# Usb.net
KiCad netlist of a schematic drawn in Altium Designer
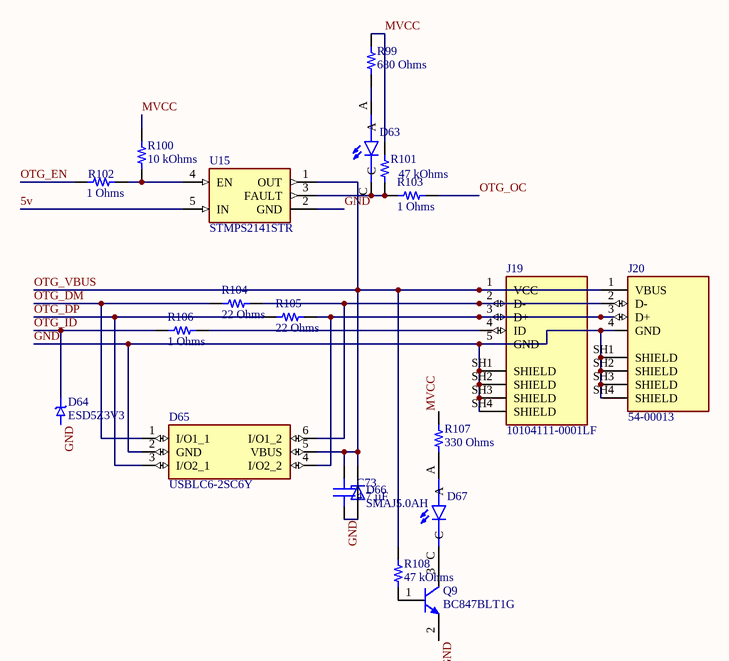
[diagram p0: Usb.SchDoc]

(export (version "E")
  (design (tool "Eeschema 10.0.6"))
  (components
    (comp (ref "C73")
      (value "4.7 µF")
      (footprint "CAP 0805_2012")
      (description "4.70UF 25.0V")
      (fields
        (field (name "PART NUMBER") "C0805X475M3RAC7800")
        (field (name "CAPACITANCE") "4.7 µF")
        (field (name "MANUFACTURER") "KEMET")
      )
      (libsource (lib "Celestial Altium Library - altium_library") (part "Capacitor"))
    )
    (comp (ref "D63")
      (value "597-3305-607F")
      (footprint "LEDC2012X70N")
      (description "LED Uni-Color Green 4-Pin Chip 0805 T/R")
      (libsource (lib "597-3305-607F") (part "597-3305-607F"))
    )
    (comp (ref "D64")
      (value "ESD5Z3V3")
      (footprint "SOD-523_DIOTEC-SEMICONDUCTOR")
      (description "ESD, SOD-523, 0.05ÂµA, 3.3V, Unidir")
      (fields (field (name "MF") "Diotec Semiconductor"))
      (libsource (lib "ESD5Z3V3") (part "ESD5Z3V3"))
    )
    (comp (ref "D65")
      (value "USBLC6-2SC6Y")
      (footprint "SOT95P280X145-6N")
      (description "17V Clamp 5A (8/20µs) Ipp Tvs Diode Surface Mount SOT-23-6")
      (fields (field (name "MF") "STMicroelectronics"))
      (libsource (lib "USBLC6-2SC6Y") (part "USBLC6-2SC6Y"))
    )
    (comp (ref "D66")
      (value "SMAJ5.0AH")
      (footprint "DIOM4325X250N")
      (libsource (lib "SMAJ5.0AH") (part "SMAJ5.0AH"))
    )
    (comp (ref "D67")
      (value "597-3305-607F")
      (footprint "LEDC2012X70N")
      (description "LED Uni-Color Green 4-Pin Chip 0805 T/R")
      (libsource (lib "597-3305-607F") (part "597-3305-607F"))
    )
    (comp (ref "J19")
      (value "10104111-0001LF")
      (footprint "AMPHENOL_10104111-0001LF")
      (fields (field (name "MF") "Amphenol"))
      (libsource (lib "10104111-0001LF") (part "10104111-0001LF"))
    )
    (comp (ref "J20")
      (value "54-00013")
      (footprint "TENSILITY_54-00013")
      (description "Connector, USB A Jack, PCB side-mount, 90 degrees, nickel shell, board lock, black insulator, tray")
      (fields (field (name "MF") "Tensility International Corporation"))
      (libsource (lib "54-00013") (part "54-00013"))
    )
    (comp (ref "Q9")
      (value "BC847BLT1G")
      (footprint "ON SEMI SOT-23-3")
      (description "TRANS NPN 45V 0.1A SOT23")
      (fields (field (name "MANUFACTURER") "ON Semiconductor"))
      (libsource (lib "Celestial Altium Library - altium_library") (part "ON SEMI NPN SOT-23-3"))
    )
    (comp (ref "R99")
      (value "680 Ohms")
      (footprint "RES 0805_2012")
      (description "RES SMD 680 OHM 0.5% 1/4W 0805")
      (fields
        (field (name "PART NUMBER") "RNCF0805DTE680R")
        (field (name "MANUFACTURER") "Stackpole Electronics Inc")
      )
      (libsource (lib "Celestial Altium Library - altium_library") (part "Resistor"))
    )
    (comp (ref "R100")
      (value "10 kOhms")
      (footprint "YAGEO RES 0805_2012")
      (description "RES SMD 10K OHM 0.5% 1/8W 0805")
      (fields (field (name "PART NUMBER") "RT0805DRD0710KL") (field (name "MANUFACTURER") "Yageo"))
      (libsource (lib "Celestial Altium Library - altium_library") (part "Resistor"))
    )
    (comp (ref "R101")
      (value "47 kOhms")
      (footprint "YAGEO RES 0805_2012")
      (description "RES SMD 47K OHM 0.5% 1/8W 0805")
      (fields (field (name "PART NUMBER") "RT0805DRD0747KL") (field (name "MANUFACTURER") "Yageo"))
      (libsource (lib "Celestial Altium Library - altium_library") (part "Resistor"))
    )
    (comp (ref "R102")
      (value "1 Ohms")
      (footprint "RES 0805_2012")
      (description "RES 1 OHM 1% 1/4W 0805")
      (fields
        (field (name "PART NUMBER") "CSR0805FK1R00")
        (field (name "MANUFACTURER") "Stackpole Electronics Inc")
      )
      (libsource (lib "Celestial Altium Library - altium_library") (part "Resistor"))
    )
    (comp (ref "R103")
      (value "1 Ohms")
      (footprint "RES 0805_2012")
      (description "RES 1 OHM 1% 1/4W 0805")
      (fields
        (field (name "PART NUMBER") "CSR0805FK1R00")
        (field (name "MANUFACTURER") "Stackpole Electronics Inc")
      )
      (libsource (lib "Celestial Altium Library - altium_library") (part "Resistor"))
    )
    (comp (ref "R104")
      (value "22 Ohms")
      (footprint "RES 0805_2012")
      (description "RES 22 OHM 5% 1/3W 0805")
      (fields
        (field (name "PART NUMBER") "CRGH0805J22R")
        (field (name "MANUFACTURER") "TE Connectivity Passive Product")
      )
      (libsource (lib "Celestial Altium Library - altium_library") (part "Resistor"))
    )
    (comp (ref "R105")
      (value "22 Ohms")
      (footprint "RES 0805_2012")
      (description "RES 22 OHM 5% 1/3W 0805")
      (fields
        (field (name "PART NUMBER") "CRGH0805J22R")
        (field (name "MANUFACTURER") "TE Connectivity Passive Product")
      )
      (libsource (lib "Celestial Altium Library - altium_library") (part "Resistor"))
    )
    (comp (ref "R106")
      (value "1 Ohms")
      (footprint "RES 0805_2012")
      (description "RES 1 OHM 1% 1/4W 0805")
      (fields
        (field (name "PART NUMBER") "CSR0805FK1R00")
        (field (name "MANUFACTURER") "Stackpole Electronics Inc")
      )
      (libsource (lib "Celestial Altium Library - altium_library") (part "Resistor"))
    )
    (comp (ref "R107")
      (value "330 Ohms")
      (footprint "RES 0805_2012")
      (description "RES SMD 330 OHM 1% 1/2W 0805")
      (fields (field (name "PART NUMBER") "CRCW0805330RFKEAHP") (field (name "MANUFACTURER") "Vishay Dale"))
      (libsource (lib "Celestial Altium Library - altium_library") (part "Resistor"))
    )
    (comp (ref "R108")
      (value "47 kOhms")
      (footprint "YAGEO RES 0805_2012")
      (description "RES SMD 47K OHM 0.5% 1/8W 0805")
      (fields (field (name "PART NUMBER") "RT0805DRD0747KL") (field (name "MANUFACTURER") "Yageo"))
      (libsource (lib "Celestial Altium Library - altium_library") (part "Resistor"))
    )
    (comp (ref "U15")
      (value "STMPS2141STR")
      (footprint "SOT95P280X145-5N")
      (description "Power Switch/Driver 1:1 N-Channel 500mA SOT-23-5")
      (fields (field (name "DIGI-KEY_PART_NUMBER") "497-6933-2-ND") (field (name "MF") "STMicroelectronics"))
      (libsource (lib "STMPS2141STR") (part "STMPS2141STR"))
    )
  )
  (nets
    (net (code "1") (name "/5v") (class "Default")
      (node (ref "U15") (pin "5") (pinfunction "IN_5") (pintype "input"))
    )
    (net (code "2") (name "/GND") (class "Default")
      (node (ref "C73") (pin "1") (pinfunction "1_1") (pintype "passive"))
      (node (ref "D64") (pin "2") (pinfunction "A_2") (pintype "passive"))
      (node (ref "D65") (pin "2") (pinfunction "GND_2") (pintype "bidirectional"))
      (node (ref "D66") (pin "A") (pinfunction "A_A") (pintype "passive"))
      (node (ref "J19") (pin "5") (pinfunction "GND_5") (pintype "power_in"))
      (node (ref "J19") (pin "SH1") (pinfunction "SHIELD_SH1") (pintype "passive"))
      (node (ref "J19") (pin "SH2") (pinfunction "SHIELD_SH2") (pintype "passive"))
      (node (ref "J19") (pin "SH3") (pinfunction "SHIELD_SH3") (pintype "passive"))
      (node (ref "J19") (pin "SH4") (pinfunction "SHIELD_SH4") (pintype "passive"))
      (node (ref "J20") (pin "4") (pinfunction "GND_4") (pintype "power_in"))
      (node (ref "J20") (pin "SH1") (pinfunction "SHIELD_SH1") (pintype "passive"))
      (node (ref "J20") (pin "SH2") (pinfunction "SHIELD_SH2") (pintype "passive"))
      (node (ref "J20") (pin "SH3") (pinfunction "SHIELD_SH3") (pintype "passive"))
      (node (ref "J20") (pin "SH4") (pinfunction "SHIELD_SH4") (pintype "passive"))
      (node (ref "Q9") (pin "2") (pinfunction "E_2") (pintype "passive"))
      (node (ref "U15") (pin "2") (pinfunction "GND_2") (pintype "power_in"))
    )
    (net (code "3") (name "/MVCC") (class "Default")
      (node (ref "R100") (pin "2") (pinfunction "2_2") (pintype "passive"))
      (node (ref "R101") (pin "2") (pinfunction "2_2") (pintype "passive"))
      (node (ref "R107") (pin "2") (pinfunction "2_2") (pintype "passive"))
      (node (ref "R99") (pin "2") (pinfunction "2_2") (pintype "passive"))
    )
    (net (code "4") (name "/OTG_DM") (class "Default")
      (node (ref "D65") (pin "1") (pinfunction "I/O1_1_1") (pintype "bidirectional"))
      (node (ref "R104") (pin "1") (pinfunction "1_1") (pintype "passive"))
    )
    (net (code "5") (name "/OTG_DP") (class "Default")
      (node (ref "D65") (pin "3") (pinfunction "I/O2_1_3") (pintype "bidirectional"))
      (node (ref "R105") (pin "1") (pinfunction "1_1") (pintype "passive"))
    )
    (net (code "6") (name "/OTG_EN") (class "Default")
      (node (ref "R102") (pin "1") (pinfunction "1_1") (pintype "passive"))
    )
    (net (code "7") (name "/OTG_ID") (class "Default")
      (node (ref "D64") (pin "1") (pinfunction "C_1") (pintype "passive"))
      (node (ref "R106") (pin "1") (pinfunction "1_1") (pintype "passive"))
    )
    (net (code "8") (name "/OTG_OC") (class "Default")
      (node (ref "R103") (pin "2") (pinfunction "2_2") (pintype "passive"))
    )
    (net (code "9") (name "/OTG_VBUS") (class "Default")
      (node (ref "C73") (pin "2") (pinfunction "2_2") (pintype "passive"))
      (node (ref "D65") (pin "5") (pinfunction "VBUS_5") (pintype "bidirectional"))
      (node (ref "D66") (pin "C") (pinfunction "C_C") (pintype "passive"))
      (node (ref "J19") (pin "1") (pinfunction "VCC_1") (pintype "power_in"))
      (node (ref "J20") (pin "1") (pinfunction "VBUS_1") (pintype "power_in"))
      (node (ref "R108") (pin "2") (pinfunction "2_2") (pintype "passive"))
      (node (ref "U15") (pin "1") (pinfunction "OUT_1") (pintype "output"))
    )
    (net (code "10") (name "Net-(D63-PadA)") (class "Default")
      (node (ref "D63") (pin "A") (pinfunction "A_A") (pintype "passive"))
      (node (ref "R99") (pin "1") (pinfunction "1_1") (pintype "passive"))
    )
    (net (code "11") (name "Net-(D65-I{slash}O1_2)") (class "Default")
      (node (ref "D65") (pin "6") (pinfunction "I/O1_2_6") (pintype "bidirectional"))
      (node (ref "J19") (pin "2") (pinfunction "D-_2") (pintype "bidirectional"))
      (node (ref "J20") (pin "2") (pinfunction "D-_2") (pintype "bidirectional"))
      (node (ref "R104") (pin "2") (pinfunction "2_2") (pintype "passive"))
    )
    (net (code "12") (name "Net-(D65-I{slash}O2_2)") (class "Default")
      (node (ref "D65") (pin "4") (pinfunction "I/O2_2_4") (pintype "bidirectional"))
      (node (ref "J19") (pin "3") (pinfunction "D+_3") (pintype "bidirectional"))
      (node (ref "J20") (pin "3") (pinfunction "D+_3") (pintype "bidirectional"))
      (node (ref "R105") (pin "2") (pinfunction "2_2") (pintype "passive"))
    )
    (net (code "13") (name "Net-(D67-PadA)") (class "Default")
      (node (ref "D67") (pin "A") (pinfunction "A_A") (pintype "passive"))
      (node (ref "R107") (pin "1") (pinfunction "1_1") (pintype "passive"))
    )
    (net (code "14") (name "Net-(J19-ID)") (class "Default")
      (node (ref "J19") (pin "4") (pinfunction "ID_4") (pintype "bidirectional"))
      (node (ref "R106") (pin "2") (pinfunction "2_2") (pintype "passive"))
    )
    (net (code "15") (name "Net-(Q9-B)") (class "Default")
      (node (ref "Q9") (pin "1") (pinfunction "B_1") (pintype "passive"))
      (node (ref "R108") (pin "1") (pinfunction "1_1") (pintype "passive"))
    )
    (net (code "16") (name "Net-(Q9-C)") (class "Default")
      (node (ref "D67") (pin "C") (pinfunction "C_C") (pintype "passive"))
      (node (ref "Q9") (pin "3") (pinfunction "C_3") (pintype "passive"))
    )
    (net (code "17") (name "Net-(U15-EN)") (class "Default")
      (node (ref "R100") (pin "1") (pinfunction "1_1") (pintype "passive"))
      (node (ref "R102") (pin "2") (pinfunction "2_2") (pintype "passive"))
      (node (ref "U15") (pin "4") (pinfunction "EN_4") (pintype "input"))
    )
    (net (code "18") (name "Net-(U15-FAULT)") (class "Default")
      (node (ref "D63") (pin "C") (pinfunction "C_C") (pintype "passive"))
      (node (ref "R101") (pin "1") (pinfunction "1_1") (pintype "passive"))
      (node (ref "R103") (pin "1") (pinfunction "1_1") (pintype "passive"))
      (node (ref "U15") (pin "3") (pinfunction "FAULT_3") (pintype "output"))
    )
  )
)
